# Memory_Display_V2.net
KiCad netlist of a schematic drawn in EAGLE
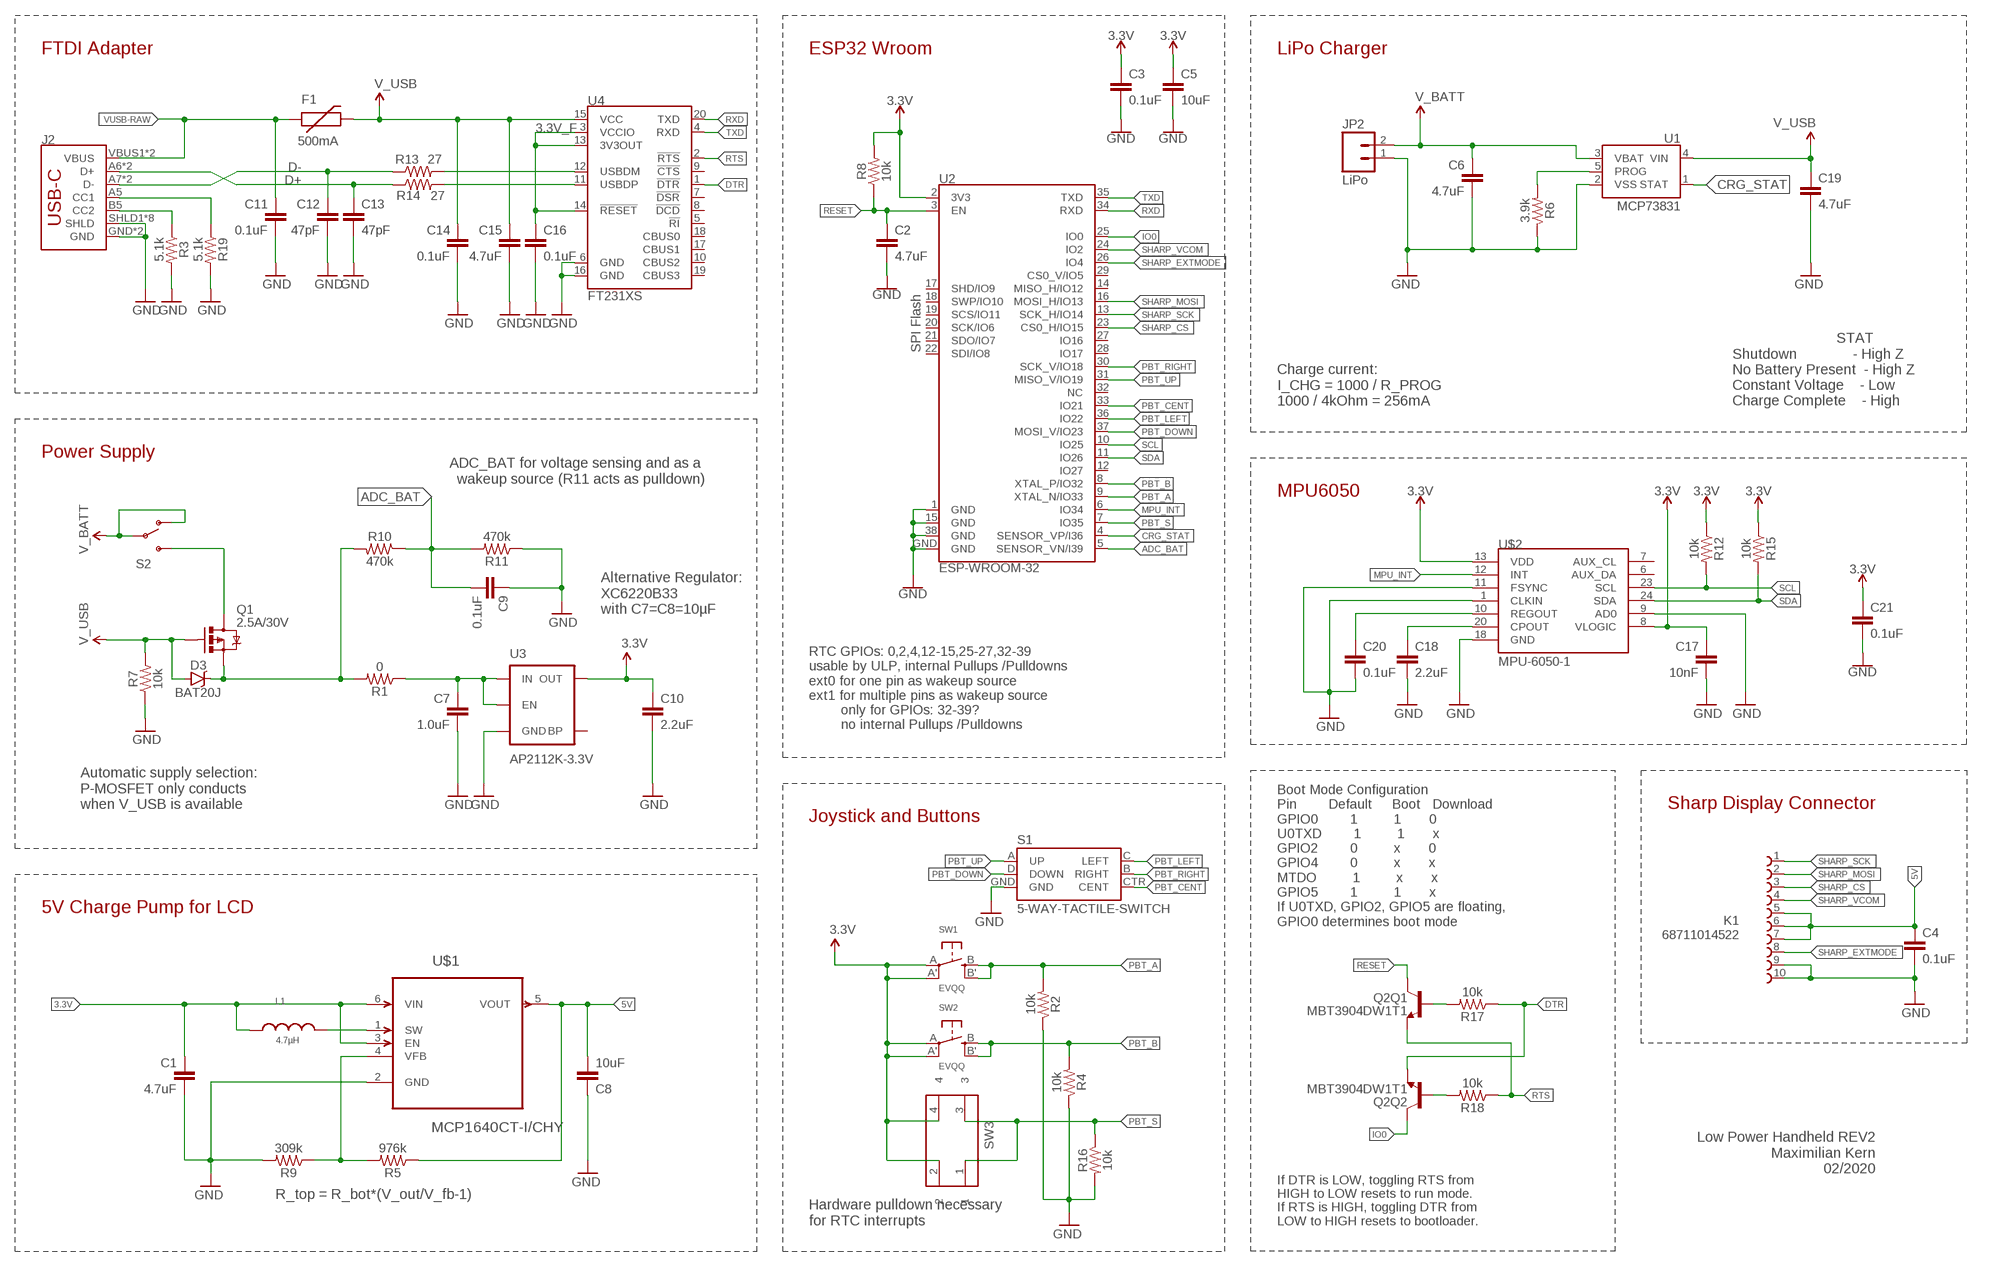
[diagram p0: schematic, sheet 1]

(export (version "E")
  (design (tool "Eeschema 10.0.6"))
  (components
    (comp (ref "C1")
      (value "4.7uF")
      (footprint "eagle-import:0603")
      (libsource (lib "eagle-import") (part "47PF-0603-50V-5%"))
    )
    (comp (ref "C2")
      (value "4.7uF")
      (footprint "eagle-import:0603")
      (libsource (lib "eagle-import") (part "0.1UF-0603-25V-(+80/-20%)"))
    )
    (comp (ref "C3")
      (value "0.1uF")
      (footprint "eagle-import:0603")
      (libsource (lib "eagle-import") (part "0.1UF-0603-25V-(+80/-20%)"))
    )
    (comp (ref "C4")
      (value "0.1uF")
      (footprint "eagle-import:0603")
      (libsource (lib "eagle-import") (part "0.1UF-0603-25V-(+80/-20%)"))
    )
    (comp (ref "C5")
      (value "10uF")
      (footprint "eagle-import:0603")
      (libsource (lib "eagle-import") (part "10UF-0603-6.3V-20%"))
    )
    (comp (ref "C6")
      (value "4.7uF")
      (footprint "eagle-import:0603")
      (libsource (lib "eagle-import") (part "4.7UF0603"))
    )
    (comp (ref "C7")
      (value "1.0uF")
      (footprint "eagle-import:0805")
      (libsource (lib "eagle-import") (part "1.0UF-0805-25V-(+80/-20%)"))
    )
    (comp (ref "C8")
      (value "10uF")
      (footprint "eagle-import:0603")
      (libsource (lib "eagle-import") (part "47PF-0603-50V-5%"))
    )
    (comp (ref "C9")
      (value "0.1uF")
      (footprint "eagle-import:0603")
      (libsource (lib "eagle-import") (part "0.1UF-0603-25V-(+80/-20%)"))
    )
    (comp (ref "C10")
      (value "2.2uF")
      (footprint "eagle-import:0805")
      (libsource (lib "eagle-import") (part "1.0UF-0805-25V-(+80/-20%)"))
    )
    (comp (ref "C11")
      (value "0.1uF")
      (footprint "eagle-import:0603")
      (libsource (lib "eagle-import") (part "0.1UF-0603-25V-(+80/-20%)"))
    )
    (comp (ref "C12")
      (value "47pF")
      (footprint "eagle-import:0603")
      (libsource (lib "eagle-import") (part "47PF-0603-50V-5%"))
    )
    (comp (ref "C13")
      (value "47pF")
      (footprint "eagle-import:0603")
      (libsource (lib "eagle-import") (part "47PF-0603-50V-5%"))
    )
    (comp (ref "C14")
      (value "0.1uF")
      (footprint "eagle-import:0603")
      (libsource (lib "eagle-import") (part "0.1UF-0603-25V-(+80/-20%)"))
    )
    (comp (ref "C15")
      (value "4.7uF")
      (footprint "eagle-import:0603-CAP")
      (libsource (lib "eagle-import") (part "4.7UF-6.3V-10%(0603)0603"))
    )
    (comp (ref "C16")
      (value "0.1uF")
      (footprint "eagle-import:0603")
      (libsource (lib "eagle-import") (part "0.1UF-0603-25V-(+80/-20%)"))
    )
    (comp (ref "C17")
      (value "10nF")
      (footprint "eagle-import:0603")
      (libsource (lib "eagle-import") (part "47PF-0603-50V-5%"))
    )
    (comp (ref "C18")
      (value "2.2uF")
      (footprint "eagle-import:0805")
      (libsource (lib "eagle-import") (part "1.0UF-0805-25V-(+80/-20%)"))
    )
    (comp (ref "C19")
      (value "4.7uF")
      (footprint "eagle-import:0603")
      (libsource (lib "eagle-import") (part "4.7UF0603"))
    )
    (comp (ref "C20")
      (value "0.1uF")
      (footprint "eagle-import:0603")
      (libsource (lib "eagle-import") (part "0.1UF-0603-25V-(+80/-20%)"))
    )
    (comp (ref "C21")
      (value "0.1uF")
      (footprint "eagle-import:0603")
      (libsource (lib "eagle-import") (part "0.1UF-0603-25V-(+80/-20%)"))
    )
    (comp (ref "D3")
      (value "BAT20J")
      (footprint "eagle-import:SOD-323")
      (libsource (lib "eagle-import") (part "DIODE-SCHOTTKY-BAT20J"))
    )
    (comp (ref "F1")
      (value "500mA")
      (footprint "eagle-import:PTC-1206")
      (libsource (lib "eagle-import") (part "PTCSMD"))
    )
    (comp (ref "J2")
      (value "USB_C16PIN")
      (footprint "eagle-import:USB-C-16P")
      (libsource (lib "eagle-import") (part "USB_C16PIN"))
    )
    (comp (ref "JP2")
      (value "LiPo")
      (footprint "eagle-import:JST-2-PTH")
      (libsource (lib "eagle-import") (part "M02JST-PTH-2"))
    )
    (comp (ref "K1")
      (value "68711014522")
      (footprint "eagle-import:68711014522")
      (libsource (lib "eagle-import") (part "68711014522"))
    )
    (comp (ref "L1")
      (value "4.7µH")
      (footprint "eagle-import:WE-TPC_2811_2813_OLD")
      (libsource (lib "eagle-import") (part "WE-TPC_2813_744029004"))
    )
    (comp (ref "Q1")
      (value "2.5A/30V")
      (footprint "eagle-import:SOT23-3")
      (libsource (lib "eagle-import") (part "MOSFET-PCHANNELDMG2307L"))
    )
    (comp (ref "Q2")
      (value "MBT3904DW1T1")
      (footprint "eagle-import:SC70-6")
      (libsource (lib "eagle-import") (part "MBT3904DW1T1"))
    )
    (comp (ref "R1")
      (value "0")
      (footprint "eagle-import:0603")
      (libsource (lib "eagle-import") (part "10KOHM-0603-1/10W-1%"))
    )
    (comp (ref "R2")
      (value "10k")
      (footprint "eagle-import:0603")
      (libsource (lib "eagle-import") (part "10KOHM-0603-1/10W-1%"))
    )
    (comp (ref "R3")
      (value "5.1k")
      (footprint "eagle-import:0603")
      (libsource (lib "eagle-import") (part "10KOHM-0603-1/10W-1%"))
    )
    (comp (ref "R4")
      (value "10k")
      (footprint "eagle-import:0603")
      (libsource (lib "eagle-import") (part "10KOHM-0603-1/10W-1%"))
    )
    (comp (ref "R5")
      (value "976k")
      (footprint "eagle-import:0603")
      (libsource (lib "eagle-import") (part "10KOHM-0603-1/10W-1%"))
    )
    (comp (ref "R6")
      (value "3.9k")
      (footprint "eagle-import:0603")
      (libsource (lib "eagle-import") (part "2.0KOHM1/10W5%(0603)"))
    )
    (comp (ref "R7")
      (value "10k")
      (footprint "eagle-import:0603")
      (libsource (lib "eagle-import") (part "10KOHM-0603-1/10W-1%"))
    )
    (comp (ref "R8")
      (value "10k")
      (footprint "eagle-import:0603")
      (libsource (lib "eagle-import") (part "10KOHM-0603-1/10W-1%"))
    )
    (comp (ref "R9")
      (value "309k")
      (footprint "eagle-import:0603")
      (libsource (lib "eagle-import") (part "10KOHM-0603-1/10W-1%"))
    )
    (comp (ref "R10")
      (value "470k")
      (footprint "eagle-import:0603")
      (libsource (lib "eagle-import") (part "10KOHM-0603-1/10W-1%"))
    )
    (comp (ref "R11")
      (value "470k")
      (footprint "eagle-import:0603")
      (libsource (lib "eagle-import") (part "10KOHM-0603-1/10W-1%"))
    )
    (comp (ref "R12")
      (value "10k")
      (footprint "eagle-import:0603")
      (libsource (lib "eagle-import") (part "10KOHM-0603-1/10W-1%"))
    )
    (comp (ref "R13")
      (value "27")
      (footprint "eagle-import:0603")
      (libsource (lib "eagle-import") (part "27OHM1/10W1%(0603)0603-RES"))
    )
    (comp (ref "R14")
      (value "27")
      (footprint "eagle-import:0603")
      (libsource (lib "eagle-import") (part "27OHM1/10W1%(0603)0603-RES"))
    )
    (comp (ref "R15")
      (value "10k")
      (footprint "eagle-import:0603")
      (libsource (lib "eagle-import") (part "10KOHM-0603-1/10W-1%"))
    )
    (comp (ref "R16")
      (value "10k")
      (footprint "eagle-import:0603")
      (libsource (lib "eagle-import") (part "10KOHM-0603-1/10W-1%"))
    )
    (comp (ref "R17")
      (value "10k")
      (footprint "eagle-import:0603")
      (libsource (lib "eagle-import") (part "10KOHM-0603-1/10W-1%"))
    )
    (comp (ref "R18")
      (value "10k")
      (footprint "eagle-import:0603")
      (libsource (lib "eagle-import") (part "10KOHM-0603-1/10W-1%"))
    )
    (comp (ref "R19")
      (value "5.1k")
      (footprint "eagle-import:0603")
      (libsource (lib "eagle-import") (part "10KOHM-0603-1/10W-1%"))
    )
    (comp (ref "S1")
      (value "5-WAY-TACTILE-SWITCH")
      (footprint "eagle-import:JOYSTICK_MINI")
      (libsource (lib "eagle-import") (part "JOYSTICK_MINI"))
    )
    (comp (ref "S2")
      (value "SWITCH-SPDT-SMD-A")
      (footprint "eagle-import:SWITCH-SPST-SMD-A")
      (libsource (lib "eagle-import") (part "SWITCH-SPDT-SMD-A"))
    )
    (comp (ref "SW1")
      (value "EVQQ")
      (footprint "eagle-import:EVQ-Q2_SMALLER")
      (libsource (lib "eagle-import") (part "SWITCH_TACT_SMT_EVQQ2_SMALL"))
    )
    (comp (ref "SW2")
      (value "EVQQ")
      (footprint "eagle-import:EVQ-Q2_SMALLER")
      (libsource (lib "eagle-import") (part "SWITCH_TACT_SMT_EVQQ2_SMALL"))
    )
    (comp (ref "SW3")
      (value "434331045822")
      (footprint "eagle-import:434331045822")
      (libsource (lib "eagle-import") (part "434331045822"))
    )
    (comp (ref "U$1")
      (value "MCP1640CT-I/CHY")
      (footprint "eagle-import:SOT95P270X145-6N")
      (libsource (lib "eagle-import") (part "MCP1640CT-I/CHY"))
    )
    (comp (ref "U$2")
      (value "MPU-6050-1")
      (footprint "eagle-import:QFN-24-4MM2")
      (libsource (lib "eagle-import") (part "MPU-6050-1"))
    )
    (comp (ref "U1")
      (value "MCP73831")
      (footprint "eagle-import:SOT23-5")
      (libsource (lib "eagle-import") (part "MCP73831"))
    )
    (comp (ref "U2")
      (value "ESP-WROOM-32")
      (footprint "eagle-import:ESP-WROOM-32")
      (libsource (lib "eagle-import") (part "ESP-WROOM-32"))
    )
    (comp (ref "U3")
      (value "AP2112K-3.3V")
      (footprint "eagle-import:SOT23-5")
      (libsource (lib "eagle-import") (part "V_REG_LDOSMD"))
    )
    (comp (ref "U4")
      (value "FT231XS")
      (footprint "eagle-import:SSOP20_L")
      (libsource (lib "eagle-import") (part "FT231XS"))
    )
  )
  (nets
    (net (code "1") (name "/3.3V_F") (class "Default")
      (node (ref "C16") (pin "1") (pinfunction "1_1") (pintype "passive"))
      (node (ref "U4") (pin "13") (pinfunction "3V3OUT_13") (pintype "bidirectional"))
      (node (ref "U4") (pin "14") (pinfunction "~{RESET}_14") (pintype "bidirectional"))
      (node (ref "U4") (pin "3") (pinfunction "VCCIO_3") (pintype "bidirectional"))
    )
    (net (code "2") (name "/D+") (class "Default")
      (node (ref "C13") (pin "1") (pinfunction "1_1") (pintype "passive"))
      (node (ref "J2") (pin "A6") (pinfunction "D+_A6") (pintype "bidirectional"))
      (node (ref "J2") (pin "B6") (pinfunction "D+_B6") (pintype "bidirectional"))
      (node (ref "R14") (pin "1") (pinfunction "1_1") (pintype "passive"))
    )
    (net (code "3") (name "/D-") (class "Default")
      (node (ref "C12") (pin "1") (pinfunction "1_1") (pintype "passive"))
      (node (ref "J2") (pin "A7") (pinfunction "D-_A7") (pintype "bidirectional"))
      (node (ref "J2") (pin "B7") (pinfunction "D-_B7") (pintype "bidirectional"))
      (node (ref "R13") (pin "1") (pinfunction "1_1") (pintype "passive"))
    )
    (net (code "4") (name "3.3V") (class "Default")
      (node (ref "C1") (pin "1") (pinfunction "1_1") (pintype "passive"))
      (node (ref "C10") (pin "1") (pinfunction "1_1") (pintype "passive"))
      (node (ref "C17") (pin "1") (pinfunction "1_1") (pintype "passive"))
      (node (ref "C21") (pin "1") (pinfunction "1_1") (pintype "passive"))
      (node (ref "C3") (pin "1") (pinfunction "1_1") (pintype "passive"))
      (node (ref "C5") (pin "1") (pinfunction "1_1") (pintype "passive"))
      (node (ref "L1") (pin "1") (pinfunction "1_1") (pintype "passive"))
      (node (ref "R12") (pin "1") (pinfunction "1_1") (pintype "passive"))
      (node (ref "R15") (pin "1") (pinfunction "1_1") (pintype "passive"))
      (node (ref "R8") (pin "2") (pinfunction "2_2") (pintype "passive"))
      (node (ref "SW1") (pin "A") (pinfunction "P_A") (pintype "passive"))
      (node (ref "SW1") (pin "A'") (pinfunction "P1_A'") (pintype "passive"))
      (node (ref "SW2") (pin "A") (pinfunction "P_A") (pintype "passive"))
      (node (ref "SW2") (pin "A'") (pinfunction "P1_A'") (pintype "passive"))
      (node (ref "SW3") (pin "2") (pinfunction "2_2") (pintype "bidirectional"))
      (node (ref "SW3") (pin "4") (pinfunction "4_4") (pintype "bidirectional"))
      (node (ref "U$1") (pin "3") (pinfunction "EN_3") (pintype "input"))
      (node (ref "U$1") (pin "6") (pinfunction "VIN_6") (pintype "input"))
      (node (ref "U$2") (pin "13") (pinfunction "VDD_13") (pintype "bidirectional"))
      (node (ref "U$2") (pin "8") (pinfunction "VLOGIC_8") (pintype "bidirectional"))
      (node (ref "U2") (pin "2") (pinfunction "3V3_2") (pintype "bidirectional"))
      (node (ref "U3") (pin "5") (pinfunction "OUT_5") (pintype "passive"))
    )
    (net (code "5") (name "5V") (class "Default")
      (node (ref "C4") (pin "1") (pinfunction "1_1") (pintype "passive"))
      (node (ref "C8") (pin "2") (pinfunction "2_2") (pintype "passive"))
      (node (ref "K1") (pin "5") (pinfunction "5_5") (pintype "passive"))
      (node (ref "K1") (pin "6") (pinfunction "6_6") (pintype "passive"))
      (node (ref "K1") (pin "7") (pinfunction "7_7") (pintype "passive"))
      (node (ref "R5") (pin "1") (pinfunction "1_1") (pintype "passive"))
      (node (ref "U$1") (pin "5") (pinfunction "VOUT_5") (pintype "output"))
    )
    (net (code "6") (name "ADC_BAT") (class "Default")
      (node (ref "C9") (pin "2") (pinfunction "2_2") (pintype "passive"))
      (node (ref "R10") (pin "1") (pinfunction "1_1") (pintype "passive"))
      (node (ref "R11") (pin "2") (pinfunction "2_2") (pintype "passive"))
      (node (ref "U2") (pin "5") (pinfunction "SENSOR_VN/I39_5") (pintype "bidirectional"))
    )
    (net (code "7") (name "CRG_STAT") (class "Default")
      (node (ref "U1") (pin "1") (pinfunction "STAT_1") (pintype "output"))
      (node (ref "U2") (pin "4") (pinfunction "SENSOR_VP/I36_4") (pintype "bidirectional"))
    )
    (net (code "8") (name "DTR") (class "Default")
      (node (ref "Q2") (pin "1") (pinfunction "E_1") (pintype "passive"))
      (node (ref "R17") (pin "1") (pinfunction "1_1") (pintype "passive"))
      (node (ref "U4") (pin "1") (pinfunction "~{DTR}_1") (pintype "bidirectional"))
    )
    (net (code "9") (name "GND") (class "Default")
      (node (ref "C1") (pin "2") (pinfunction "2_2") (pintype "passive"))
      (node (ref "C10") (pin "2") (pinfunction "2_2") (pintype "passive"))
      (node (ref "C11") (pin "2") (pinfunction "2_2") (pintype "passive"))
      (node (ref "C12") (pin "2") (pinfunction "2_2") (pintype "passive"))
      (node (ref "C13") (pin "2") (pinfunction "2_2") (pintype "passive"))
      (node (ref "C14") (pin "2") (pinfunction "2_2") (pintype "passive"))
      (node (ref "C15") (pin "2") (pinfunction "2_2") (pintype "passive"))
      (node (ref "C16") (pin "2") (pinfunction "2_2") (pintype "passive"))
      (node (ref "C17") (pin "2") (pinfunction "2_2") (pintype "passive"))
      (node (ref "C18") (pin "2") (pinfunction "2_2") (pintype "passive"))
      (node (ref "C19") (pin "2") (pinfunction "2_2") (pintype "passive"))
      (node (ref "C2") (pin "2") (pinfunction "2_2") (pintype "passive"))
      (node (ref "C20") (pin "2") (pinfunction "2_2") (pintype "passive"))
      (node (ref "C21") (pin "2") (pinfunction "2_2") (pintype "passive"))
      (node (ref "C3") (pin "2") (pinfunction "2_2") (pintype "passive"))
      (node (ref "C4") (pin "2") (pinfunction "2_2") (pintype "passive"))
      (node (ref "C5") (pin "2") (pinfunction "2_2") (pintype "passive"))
      (node (ref "C6") (pin "2") (pinfunction "2_2") (pintype "passive"))
      (node (ref "C7") (pin "2") (pinfunction "2_2") (pintype "passive"))
      (node (ref "C8") (pin "1") (pinfunction "1_1") (pintype "passive"))
      (node (ref "C9") (pin "1") (pinfunction "1_1") (pintype "passive"))
      (node (ref "J2") (pin "GND") (pinfunction "GND_GND") (pintype "bidirectional"))
      (node (ref "J2") (pin "GND2") (pinfunction "GND_GND2") (pintype "bidirectional"))
      (node (ref "J2") (pin "SHLD1") (pinfunction "SHLD_SHLD1") (pintype "bidirectional"))
      (node (ref "J2") (pin "SHLD2") (pinfunction "SHLD_SHLD2") (pintype "bidirectional"))
      (node (ref "J2") (pin "SHLD3") (pinfunction "SHLD_SHLD3") (pintype "bidirectional"))
      (node (ref "J2") (pin "SHLD4") (pinfunction "SHLD_SHLD4") (pintype "bidirectional"))
      (node (ref "J2") (pin "SHLD5") (pinfunction "SHLD_SHLD5") (pintype "bidirectional"))
      (node (ref "J2") (pin "SHLD6") (pinfunction "SHLD_SHLD6") (pintype "bidirectional"))
      (node (ref "J2") (pin "SHLD7") (pinfunction "SHLD_SHLD7") (pintype "bidirectional"))
      (node (ref "J2") (pin "SHLD8") (pinfunction "SHLD_SHLD8") (pintype "bidirectional"))
      (node (ref "JP2") (pin "1") (pinfunction "1_1") (pintype "passive"))
      (node (ref "K1") (pin "10") (pinfunction "10_10") (pintype "passive"))
      (node (ref "K1") (pin "9") (pinfunction "9_9") (pintype "passive"))
      (node (ref "R11") (pin "1") (pinfunction "1_1") (pintype "passive"))
      (node (ref "R16") (pin "2") (pinfunction "2_2") (pintype "passive"))
      (node (ref "R19") (pin "2") (pinfunction "2_2") (pintype "passive"))
      (node (ref "R2") (pin "1") (pinfunction "1_1") (pintype "passive"))
      (node (ref "R3") (pin "2") (pinfunction "2_2") (pintype "passive"))
      (node (ref "R4") (pin "1") (pinfunction "1_1") (pintype "passive"))
      (node (ref "R6") (pin "1") (pinfunction "1_1") (pintype "passive"))
      (node (ref "R7") (pin "1") (pinfunction "1_1") (pintype "passive"))
      (node (ref "R9") (pin "2") (pinfunction "2_2") (pintype "passive"))
      (node (ref "S1") (pin "GND") (pinfunction "GND_GND") (pintype "bidirectional"))
      (node (ref "U$1") (pin "2") (pinfunction "GND_2") (pintype "passive"))
      (node (ref "U$2") (pin "1") (pinfunction "CLKIN_1") (pintype "bidirectional"))
      (node (ref "U$2") (pin "11") (pinfunction "FSYNC_11") (pintype "bidirectional"))
      (node (ref "U$2") (pin "18") (pinfunction "GND_18") (pintype "bidirectional"))
      (node (ref "U$2") (pin "9") (pinfunction "AD0_9") (pintype "bidirectional"))
      (node (ref "U1") (pin "2") (pinfunction "VSS_2") (pintype "power_in"))
      (node (ref "U2") (pin "1") (pinfunction "GND_1") (pintype "bidirectional"))
      (node (ref "U2") (pin "15") (pinfunction "GND_15") (pintype "bidirectional"))
      (node (ref "U2") (pin "38") (pinfunction "GND_38") (pintype "bidirectional"))
      (node (ref "U2") (pin "GND") (pinfunction "GND_GND") (pintype "bidirectional"))
      (node (ref "U3") (pin "2") (pinfunction "GND_2") (pintype "input"))
      (node (ref "U4") (pin "16") (pinfunction "GND_16") (pintype "bidirectional"))
      (node (ref "U4") (pin "6") (pinfunction "GND_6") (pintype "bidirectional"))
    )
    (net (code "10") (name "IO0") (class "Default")
      (node (ref "Q2") (pin "6") (pinfunction "C_6") (pintype "passive"))
      (node (ref "U2") (pin "25") (pinfunction "IO0_25") (pintype "bidirectional"))
    )
    (net (code "11") (name "MPU_INT") (class "Default")
      (node (ref "U$2") (pin "12") (pinfunction "INT_12") (pintype "bidirectional"))
      (node (ref "U2") (pin "6") (pinfunction "IO34_6") (pintype "bidirectional"))
    )
    (net (code "12") (name "Net-(J2-CC1)") (class "Default")
      (node (ref "J2") (pin "A5") (pinfunction "CC1_A5") (pintype "bidirectional"))
      (node (ref "R19") (pin "1") (pinfunction "1_1") (pintype "passive"))
    )
    (net (code "13") (name "Net-(J2-CC2)") (class "Default")
      (node (ref "J2") (pin "B5") (pinfunction "CC2_B5") (pintype "bidirectional"))
      (node (ref "R3") (pin "1") (pinfunction "1_1") (pintype "passive"))
    )
    (net (code "14") (name "Net-(Q1-D)") (class "Default")
      (node (ref "Q1") (pin "3") (pinfunction "D_3") (pintype "passive"))
      (node (ref "S2") (pin "3") (pinfunction "S_3") (pintype "passive"))
    )
    (net (code "15") (name "Net-(Q1-S)") (class "Default")
      (node (ref "D3") (pin "C") (pinfunction "C_C") (pintype "passive"))
      (node (ref "Q1") (pin "2") (pinfunction "S_2") (pintype "passive"))
      (node (ref "R1") (pin "2") (pinfunction "2_2") (pintype "passive"))
      (node (ref "R10") (pin "2") (pinfunction "2_2") (pintype "passive"))
    )
    (net (code "16") (name "Net-(Q2A-B)") (class "Default")
      (node (ref "Q2") (pin "5") (pinfunction "B_5") (pintype "passive"))
      (node (ref "R17") (pin "2") (pinfunction "2_2") (pintype "passive"))
    )
    (net (code "17") (name "Net-(Q2B-B)") (class "Default")
      (node (ref "Q2") (pin "2") (pinfunction "B_2") (pintype "passive"))
      (node (ref "R18") (pin "2") (pinfunction "2_2") (pintype "passive"))
    )
    (net (code "18") (name "Net-(U$1-SW)") (class "Default")
      (node (ref "L1") (pin "2") (pinfunction "2_2") (pintype "passive"))
      (node (ref "U$1") (pin "1") (pinfunction "SW_1") (pintype "input"))
    )
    (net (code "19") (name "Net-(U$1-VFB)") (class "Default")
      (node (ref "R5") (pin "2") (pinfunction "2_2") (pintype "passive"))
      (node (ref "R9") (pin "1") (pinfunction "1_1") (pintype "passive"))
      (node (ref "U$1") (pin "4") (pinfunction "VFB_4") (pintype "input"))
    )
    (net (code "20") (name "Net-(U$2-CPOUT)") (class "Default")
      (node (ref "C18") (pin "1") (pinfunction "1_1") (pintype "passive"))
      (node (ref "U$2") (pin "20") (pinfunction "CPOUT_20") (pintype "bidirectional"))
    )
    (net (code "21") (name "Net-(U$2-REGOUT)") (class "Default")
      (node (ref "C20") (pin "1") (pinfunction "1_1") (pintype "passive"))
      (node (ref "U$2") (pin "10") (pinfunction "REGOUT_10") (pintype "bidirectional"))
    )
    (net (code "22") (name "Net-(U1-PROG)") (class "Default")
      (node (ref "R6") (pin "2") (pinfunction "2_2") (pintype "passive"))
      (node (ref "U1") (pin "5") (pinfunction "PROG_5") (pintype "input"))
    )
    (net (code "23") (name "Net-(U3-EN)") (class "Default")
      (node (ref "C7") (pin "1") (pinfunction "1_1") (pintype "passive"))
      (node (ref "R1") (pin "1") (pinfunction "1_1") (pintype "passive"))
      (node (ref "U3") (pin "1") (pinfunction "IN_1") (pintype "input"))
      (node (ref "U3") (pin "3") (pinfunction "EN_3") (pintype "input"))
    )
    (net (code "24") (name "Net-(U4-USBDM)") (class "Default")
      (node (ref "R13") (pin "2") (pinfunction "2_2") (pintype "passive"))
      (node (ref "U4") (pin "12") (pinfunction "USBDM_12") (pintype "bidirectional"))
    )
    (net (code "25") (name "Net-(U4-USBDP)") (class "Default")
      (node (ref "R14") (pin "2") (pinfunction "2_2") (pintype "passive"))
      (node (ref "U4") (pin "11") (pinfunction "USBDP_11") (pintype "bidirectional"))
    )
    (net (code "26") (name "PBT_A") (class "Default")
      (node (ref "R2") (pin "2") (pinfunction "2_2") (pintype "passive"))
      (node (ref "SW1") (pin "B") (pinfunction "S_B") (pintype "passive"))
      (node (ref "SW1") (pin "B'") (pinfunction "S1_B'") (pintype "passive"))
      (node (ref "U2") (pin "9") (pinfunction "XTAL_N/IO33_9") (pintype "bidirectional"))
    )
    (net (code "27") (name "PBT_B") (class "Default")
      (node (ref "R4") (pin "2") (pinfunction "2_2") (pintype "passive"))
      (node (ref "SW2") (pin "B") (pinfunction "S_B") (pintype "passive"))
      (node (ref "SW2") (pin "B'") (pinfunction "S1_B'") (pintype "passive"))
      (node (ref "U2") (pin "8") (pinfunction "XTAL_P/IO32_8") (pintype "bidirectional"))
    )
    (net (code "28") (name "PBT_CENT") (class "Default")
      (node (ref "S1") (pin "CTR") (pinfunction "CENT_CTR") (pintype "bidirectional"))
      (node (ref "U2") (pin "33") (pinfunction "IO21_33") (pintype "bidirectional"))
    )
    (net (code "29") (name "PBT_DOWN") (class "Default")
      (node (ref "S1") (pin "D") (pinfunction "DOWN_D") (pintype "bidirectional"))
      (node (ref "U2") (pin "37") (pinfunction "MOSI_V/IO23_37") (pintype "bidirectional"))
    )
    (net (code "30") (name "PBT_LEFT") (class "Default")
      (node (ref "S1") (pin "C") (pinfunction "LEFT_C") (pintype "bidirectional"))
      (node (ref "U2") (pin "36") (pinfunction "IO22_36") (pintype "bidirectional"))
    )
    (net (code "31") (name "PBT_RIGHT") (class "Default")
      (node (ref "S1") (pin "B") (pinfunction "RIGHT_B") (pintype "bidirectional"))
      (node (ref "U2") (pin "30") (pinfunction "SCK_V/IO18_30") (pintype "bidirectional"))
    )
    (net (code "32") (name "PBT_S") (class "Default")
      (node (ref "R16") (pin "1") (pinfunction "1_1") (pintype "passive"))
      (node (ref "SW3") (pin "1") (pinfunction "1_1") (pintype "bidirectional"))
      (node (ref "SW3") (pin "3") (pinfunction "3_3") (pintype "bidirectional"))
      (node (ref "U2") (pin "7") (pinfunction "IO35_7") (pintype "bidirectional"))
    )
    (net (code "33") (name "PBT_UP") (class "Default")
      (node (ref "S1") (pin "A") (pinfunction "UP_A") (pintype "bidirectional"))
      (node (ref "U2") (pin "31") (pinfunction "MISO_V/IO19_31") (pintype "bidirectional"))
    )
    (net (code "34") (name "RESET") (class "Default")
      (node (ref "C2") (pin "1") (pinfunction "1_1") (pintype "passive"))
      (node (ref "Q2") (pin "3") (pinfunction "C_3") (pintype "passive"))
      (node (ref "R8") (pin "1") (pinfunction "1_1") (pintype "passive"))
      (node (ref "U2") (pin "3") (pinfunction "EN_3") (pintype "bidirectional"))
    )
    (net (code "35") (name "RTS") (class "Default")
      (node (ref "Q2") (pin "4") (pinfunction "E_4") (pintype "passive"))
      (node (ref "R18") (pin "1") (pinfunction "1_1") (pintype "passive"))
      (node (ref "U4") (pin "2") (pinfunction "~{RTS}_2") (pintype "bidirectional"))
    )
    (net (code "36") (name "RXD") (class "Default")
      (node (ref "U2") (pin "34") (pinfunction "RXD_34") (pintype "bidirectional"))
      (node (ref "U4") (pin "20") (pinfunction "TXD_20") (pintype "bidirectional"))
    )
    (net (code "37") (name "SCL") (class "Default")
      (node (ref "R12") (pin "2") (pinfunction "2_2") (pintype "passive"))
      (node (ref "U$2") (pin "23") (pinfunction "SCL_23") (pintype "bidirectional"))
      (node (ref "U2") (pin "10") (pinfunction "IO25_10") (pintype "bidirectional"))
    )
    (net (code "38") (name "SDA") (class "Default")
      (node (ref "R15") (pin "2") (pinfunction "2_2") (pintype "passive"))
      (node (ref "U$2") (pin "24") (pinfunction "SDA_24") (pintype "bidirectional"))
      (node (ref "U2") (pin "11") (pinfunction "IO26_11") (pintype "bidirectional"))
    )
    (net (code "39") (name "SHARP_CS") (class "Default")
      (node (ref "K1") (pin "3") (pinfunction "3_3") (pintype "passive"))
      (node (ref "U2") (pin "23") (pinfunction "CS0_H/IO15_23") (pintype "bidirectional"))
    )
    (net (code "40") (name "SHARP_EXTMODE") (class "Default")
      (node (ref "K1") (pin "8") (pinfunction "8_8") (pintype "passive"))
      (node (ref "U2") (pin "26") (pinfunction "IO4_26") (pintype "bidirectional"))
    )
    (net (code "41") (name "SHARP_MOSI") (class "Default")
      (node (ref "K1") (pin "2") (pinfunction "2_2") (pintype "passive"))
      (node (ref "U2") (pin "16") (pinfunction "MOSI_H/IO13_16") (pintype "bidirectional"))
    )
    (net (code "42") (name "SHARP_SCK") (class "Default")
      (node (ref "K1") (pin "1") (pinfunction "1_1") (pintype "passive"))
      (node (ref "U2") (pin "13") (pinfunction "SCK_H/IO14_13") (pintype "bidirectional"))
    )
    (net (code "43") (name "SHARP_VCOM") (class "Default")
      (node (ref "K1") (pin "4") (pinfunction "4_4") (pintype "passive"))
      (node (ref "U2") (pin "24") (pinfunction "IO2_24") (pintype "bidirectional"))
    )
    (net (code "44") (name "TXD") (class "Default")
      (node (ref "U2") (pin "35") (pinfunction "TXD_35") (pintype "bidirectional"))
      (node (ref "U4") (pin "4") (pinfunction "RXD_4") (pintype "bidirectional"))
    )
    (net (code "45") (name "VUSB-RAW") (class "Default")
      (node (ref "C11") (pin "1") (pinfunction "1_1") (pintype "passive"))
      (node (ref "F1") (pin "1") (pinfunction "1_1") (pintype "bidirectional"))
      (node (ref "J2") (pin "VBUS1") (pinfunction "VBUS_VBUS1") (pintype "bidirectional"))
      (node (ref "J2") (pin "VBUS2") (pinfunction "VBUS_VBUS2") (pintype "bidirectional"))
    )
    (net (code "46") (name "V_BATT") (class "Default")
      (node (ref "C6") (pin "1") (pinfunction "1_1") (pintype "passive"))
      (node (ref "JP2") (pin "2") (pinfunction "2_2") (pintype "passive"))
      (node (ref "S2") (pin "1") (pinfunction "O_1") (pintype "passive"))
      (node (ref "S2") (pin "2") (pinfunction "P_2") (pintype "passive"))
      (node (ref "U1") (pin "3") (pinfunction "VBAT_3") (pintype "power_in"))
    )
    (net (code "47") (name "V_USB") (class "Default")
      (node (ref "C14") (pin "1") (pinfunction "1_1") (pintype "passive"))
      (node (ref "C15") (pin "1") (pinfunction "1_1") (pintype "passive"))
      (node (ref "C19") (pin "1") (pinfunction "1_1") (pintype "passive"))
      (node (ref "D3") (pin "A") (pinfunction "A_A") (pintype "passive"))
      (node (ref "F1") (pin "2") (pinfunction "2_2") (pintype "bidirectional"))
      (node (ref "Q1") (pin "1") (pinfunction "G_1") (pintype "passive"))
      (node (ref "R7") (pin "2") (pinfunction "2_2") (pintype "passive"))
      (node (ref "U1") (pin "4") (pinfunction "VIN_4") (pintype "power_in"))
      (node (ref "U4") (pin "15") (pinfunction "VCC_15") (pintype "bidirectional"))
    )
    (net (code "48") (name "unconnected-(U$2-AUX_CL-Pad7)") (class "Default")
      (node (ref "U$2") (pin "7") (pinfunction "AUX_CL_7") (pintype "bidirectional"))
    )
    (net (code "49") (name "unconnected-(U$2-AUX_DA-Pad6)") (class "Default")
      (node (ref "U$2") (pin "6") (pinfunction "AUX_DA_6") (pintype "bidirectional"))
    )
    (net (code "50") (name "unconnected-(U2-CS0_V{slash}IO5-Pad29)") (class "Default")
      (node (ref "U2") (pin "29") (pinfunction "CS0_V/IO5_29") (pintype "bidirectional"))
    )
    (net (code "51") (name "unconnected-(U2-IO16-Pad27)") (class "Default")
      (node (ref "U2") (pin "27") (pinfunction "IO16_27") (pintype "bidirectional"))
    )
    (net (code "52") (name "unconnected-(U2-IO17-Pad28)") (class "Default")
      (node (ref "U2") (pin "28") (pinfunction "IO17_28") (pintype "bidirectional"))
    )
    (net (code "53") (name "unconnected-(U2-IO27-Pad12)") (class "Default")
      (node (ref "U2") (pin "12") (pinfunction "IO27_12") (pintype "bidirectional"))
    )
    (net (code "54") (name "unconnected-(U2-MISO_H{slash}IO12-Pad14)") (class "Default")
      (node (ref "U2") (pin "14") (pinfunction "MISO_H/IO12_14") (pintype "bidirectional"))
    )
    (net (code "55") (name "unconnected-(U2-NC-Pad32)") (class "Default")
      (node (ref "U2") (pin "32") (pinfunction "NC_32") (pintype "bidirectional"))
    )
    (net (code "56") (name "unconnected-(U2-SCK{slash}IO6-Pad20)") (class "Default")
      (node (ref "U2") (pin "20") (pinfunction "SCK/IO6_20") (pintype "bidirectional"))
    )
    (net (code "57") (name "unconnected-(U2-SCS{slash}IO11-Pad19)") (class "Default")
      (node (ref "U2") (pin "19") (pinfunction "SCS/IO11_19") (pintype "bidirectional"))
    )
    (net (code "58") (name "unconnected-(U2-SDI{slash}IO8-Pad22)") (class "Default")
      (node (ref "U2") (pin "22") (pinfunction "SDI/IO8_22") (pintype "bidirectional"))
    )
    (net (code "59") (name "unconnected-(U2-SDO{slash}IO7-Pad21)") (class "Default")
      (node (ref "U2") (pin "21") (pinfunction "SDO/IO7_21") (pintype "bidirectional"))
    )
    (net (code "60") (name "unconnected-(U2-SHD{slash}IO9-Pad17)") (class "Default")
      (node (ref "U2") (pin "17") (pinfunction "SHD/IO9_17") (pintype "bidirectional"))
    )
    (net (code "61") (name "unconnected-(U2-SWP{slash}IO10-Pad18)") (class "Default")
      (node (ref "U2") (pin "18") (pinfunction "SWP/IO10_18") (pintype "bidirectional"))
    )
    (net (code "62") (name "unconnected-(U3-BP-Pad4)") (class "Default")
      (node (ref "U3") (pin "4") (pinfunction "BP_4") (pintype "input"))
    )
    (net (code "63") (name "unconnected-(U4-CBUS0-Pad18)") (class "Default")
      (node (ref "U4") (pin "18") (pinfunction "CBUS0_18") (pintype "bidirectional"))
    )
    (net (code "64") (name "unconnected-(U4-CBUS1-Pad17)") (class "Default")
      (node (ref "U4") (pin "17") (pinfunction "CBUS1_17") (pintype "bidirectional"))
    )
    (net (code "65") (name "unconnected-(U4-CBUS2-Pad10)") (class "Default")
      (node (ref "U4") (pin "10") (pinfunction "CBUS2_10") (pintype "bidirectional"))
    )
    (net (code "66") (name "unconnected-(U4-CBUS3-Pad19)") (class "Default")
      (node (ref "U4") (pin "19") (pinfunction "CBUS3_19") (pintype "bidirectional"))
    )
    (net (code "67") (name "unconnected-(U4-~{CTS}-Pad9)") (class "Default")
      (node (ref "U4") (pin "9") (pinfunction "~{CTS}_9") (pintype "bidirectional"))
    )
    (net (code "68") (name "unconnected-(U4-~{DCD}-Pad8)") (class "Default")
      (node (ref "U4") (pin "8") (pinfunction "~{DCD}_8") (pintype "bidirectional"))
    )
    (net (code "69") (name "unconnected-(U4-~{DSR}-Pad7)") (class "Default")
      (node (ref "U4") (pin "7") (pinfunction "~{DSR}_7") (pintype "bidirectional"))
    )
    (net (code "70") (name "unconnected-(U4-~{RI}-Pad5)") (class "Default")
      (node (ref "U4") (pin "5") (pinfunction "~{RI}_5") (pintype "bidirectional"))
    )
  )
)
